# Power.net
KiCad netlist of a schematic drawn in Altium Designer
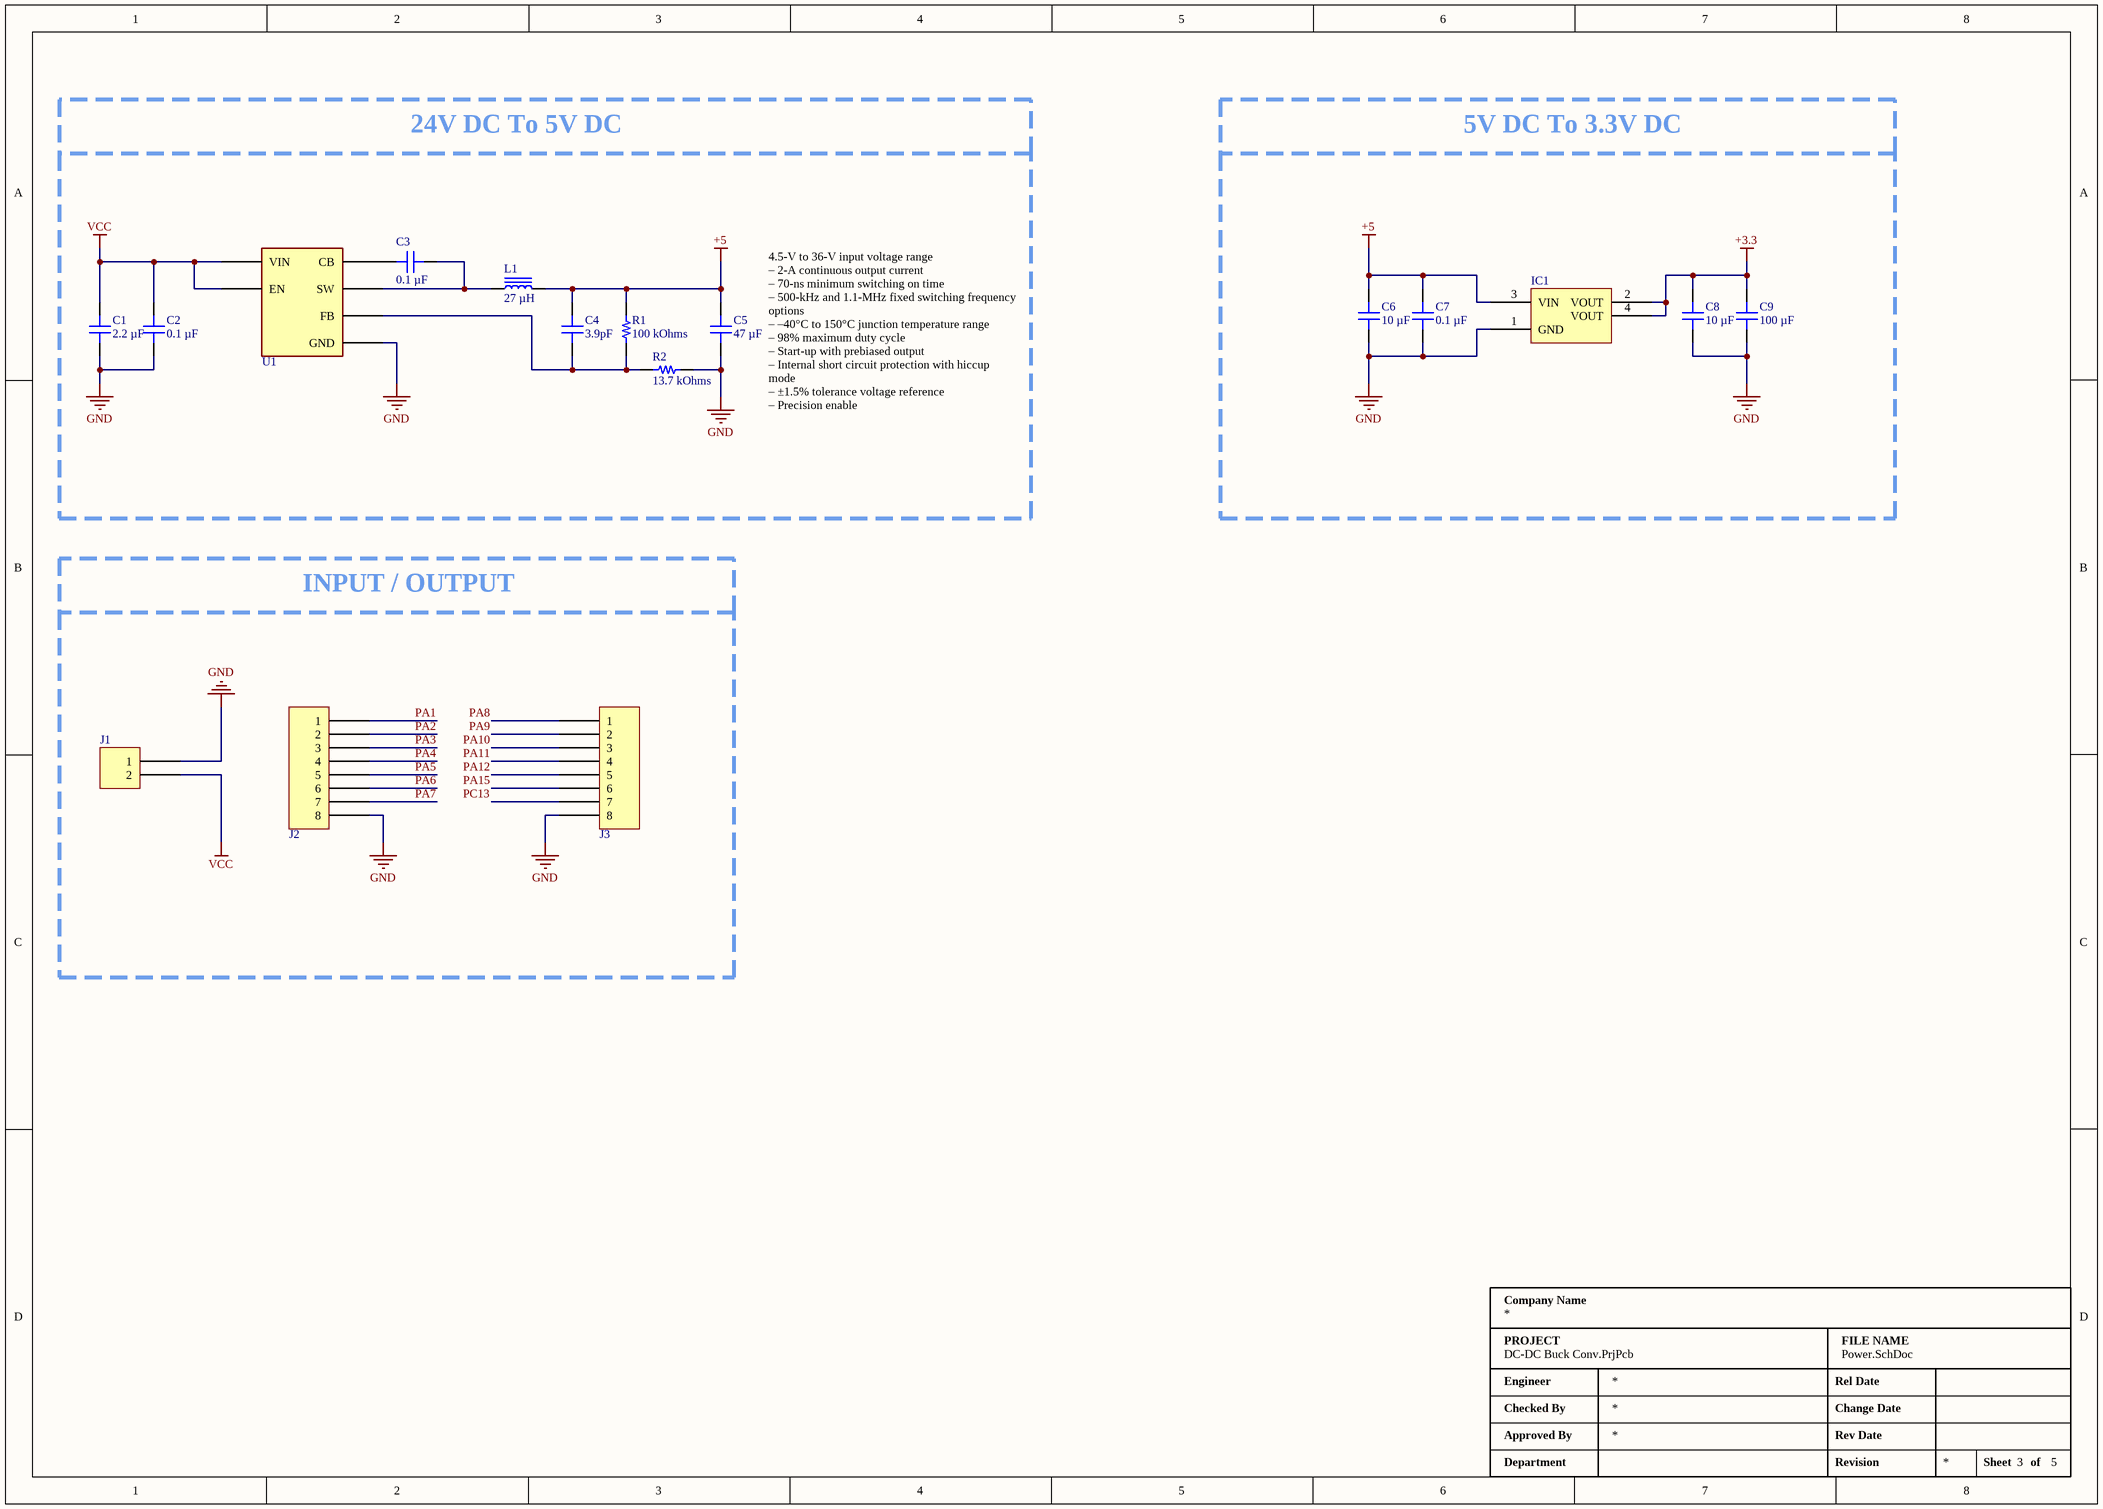
[diagram p0: Power.SchDoc]

(export (version "E")
  (design (tool "Eeschema 10.0.6"))
  (components
    (comp (ref "C1")
      (value "2.2 µF")
      (footprint "CAP 1206_3216 - 0.8MM")
      (description "CAP CER 2.2UF 50V X7R 1206")
      (fields
        (field (name "PART NUMBER") "CL31B225KBHVPNE")
        (field (name "CAPACITANCE") "2.2 µF")
        (field (name "MANUFACTURER") "Samsung Electro-Mechanics")
      )
      (libsource (lib "Celestial Altium Library - altium_library") (part "Capacitor"))
    )
    (comp (ref "C2")
      (value "0.1 µF")
      (footprint "CAP 0603_1608")
      (description "CAP CER 0603 0.1UF 50V X7R 10%")
      (fields
        (field (name "PART NUMBER") "C0603X104K5RAC3316")
        (field (name "CAPACITANCE") "0.1 µF")
        (field (name "MANUFACTURER") "KEMET")
      )
      (libsource (lib "Celestial Altium Library - altium_library") (part "Capacitor"))
    )
    (comp (ref "C3")
      (value "0.1 µF")
      (footprint "CAP 0402_1005")
      (description "CAP CER 0402 0.1UF 16V X7R 10%")
      (fields
        (field (name "PART NUMBER") "C0402C104K4RECAUTO")
        (field (name "CAPACITANCE") "0.1 µF")
        (field (name "MANUFACTURER") "KEMET")
      )
      (libsource (lib "Celestial Altium Library - altium_library") (part "Capacitor"))
    )
    (comp (ref "C4")
      (value "3.9pF")
      (footprint "CAP 0402_1005")
      (description "CAP CER 3.9PF 25V NP0 0402")
      (fields
        (field (name "PART NUMBER") "04023U3R9BAT2A")
        (field (name "CAPACITANCE") "3.9pF")
        (field (name "MANUFACTURER") "AVX Corporation")
      )
      (libsource (lib "Celestial Altium Library - altium_library") (part "Capacitor"))
    )
    (comp (ref "C5")
      (value "47 µF")
      (footprint "MURATA - GRM32E")
      (description "CAP CER 47UF 16V X6S 1210")
      (fields
        (field (name "PART NUMBER") "GRM32EC81C476KE15L")
        (field (name "MANUFACTURER") "Murata Electronics")
      )
      (libsource (lib "Celestial Altium Library - altium_library") (part "Capacitor"))
    )
    (comp (ref "C6")
      (value "10 µF")
      (footprint "MURATA GRM21B 0805_2012")
      (description "CAP CER 10UF 50V X5R 0805")
      (fields
        (field (name "PART NUMBER") "GRM21BR61H106KE43L")
        (field (name "CAPACITANCE") "10 µF")
        (field (name "MANUFACTURER") "Murata Electronics")
      )
      (libsource (lib "Celestial Altium Library - altium_library") (part "Capacitor"))
    )
    (comp (ref "C7")
      (value "0.1 µF")
      (footprint "CAP 0805_2012")
      (description "CAP CER 0805 0.1UF 100V X7R 5%")
      (fields
        (field (name "PART NUMBER") "C0805C104J1RECAUTO")
        (field (name "CAPACITANCE") "0.1 µF")
        (field (name "MANUFACTURER") "KEMET")
      )
      (libsource (lib "Celestial Altium Library - altium_library") (part "Capacitor"))
    )
    (comp (ref "C8")
      (value "10 µF")
      (footprint "MURATA GRM21B 0805_2012")
      (description "CAP CER 10UF 50V X5R 0805")
      (fields
        (field (name "PART NUMBER") "GRM21BR61H106KE43L")
        (field (name "CAPACITANCE") "10 µF")
        (field (name "MANUFACTURER") "Murata Electronics")
      )
      (libsource (lib "Celestial Altium Library - altium_library") (part "Capacitor"))
    )
    (comp (ref "C9")
      (value "100 µF")
      (footprint "MURATA GRM21B 0805_2012")
      (description "CAP CER 100UF 6.3V X5R 0805")
      (fields
        (field (name "PART NUMBER") "GRM21BR60J107ME15K")
        (field (name "CAPACITANCE") "100 µF")
        (field (name "MANUFACTURER") "Murata Electronics")
      )
      (libsource (lib "Celestial Altium Library - altium_library") (part "Capacitor"))
    )
    (comp (ref "IC1")
      (value "LD1117AS33TR")
      (footprint "ST SOT-223")
      (description "IC REG LINEAR 3.3V 1A SOT223")
      (fields (field (name "MANUFACTURER") "STMicroelectronics"))
      (libsource (lib "Celestial Altium Library - altium_library") (part "ST LD1117"))
    )
    (comp (ref "J1")
      (value "282837-2")
      (footprint "TE 282837-2")
      (description "TERM BLK 2P SIDE ENT 5.08MM PCB")
      (fields (field (name "MANUFACTURER") "TE Connectivity AMP Connectors") (field (name "VOLTAGE") "300 V"))
      (libsource (lib "Celestial Altium Library - altium_library") (part "2 Pin"))
    )
    (comp (ref "J2")
      (value "SSW-108-03-T-S")
      (footprint "SAMTEC SSW-108-03-T-S")
      (description "CONN RCPT 8POS 0.1 TIN PCB")
      (fields (field (name "MANUFACTURER") "Samtec Inc."))
      (libsource (lib "Celestial Altium Library - altium_library") (part "8 Pin"))
    )
    (comp (ref "J3")
      (value "SSW-108-03-T-S")
      (footprint "SAMTEC SSW-108-03-T-S")
      (description "CONN RCPT 8POS 0.1 TIN PCB")
      (fields (field (name "MANUFACTURER") "Samtec Inc."))
      (libsource (lib "") (part "8 Pin_1"))
    )
    (comp (ref "L1")
      (value "27 µH")
      (footprint "BOURNS SRR6028")
      (description "FIXED IND 27UH 1.2A 130 MOHM SMD")
      (fields (field (name "PART NUMBER") "SRR6028-270Y") (field (name "MANUFACTURER") "Bourns Inc."))
      (libsource (lib "Celestial Altium Library - altium_library") (part "Inductor"))
    )
    (comp (ref "R1")
      (value "100 kOhms")
      (footprint "YAGEO RES 0402_1005")
      (description "RES 162K OHM 1% 1/16W 0402")
      (fields (field (name "PART NUMBER") "RC0402FR-07162KL") (field (name "MANUFACTURER") "Yageo"))
      (libsource (lib "Celestial Altium Library - altium_library") (part "Resistor"))
    )
    (comp (ref "R2")
      (value "13.7 kOhms")
      (footprint "YAGEO RES 0402_1005")
      (description "RES 22.1K OHM 1% 1/16W 0402")
      (fields (field (name "PART NUMBER") "RC0402FR-0722K1L") (field (name "MANUFACTURER") "Yageo"))
      (libsource (lib "Celestial Altium Library - altium_library") (part "Resistor"))
    )
    (comp (ref "U1")
      (value "IC REG BUCK ADJ 2A SOT23")
      (footprint "SOT-23-6 Thin")
      (libsource (lib "DcDcBuck") (part "LMR51420XDDCR"))
    )
  )
  (nets
    (net (code "1") (name "+3.3") (class "Default")
      (node (ref "C8") (pin "2") (pinfunction "2_2") (pintype "passive"))
      (node (ref "C9") (pin "2") (pinfunction "2_2") (pintype "passive"))
      (node (ref "IC1") (pin "2") (pinfunction "VOUT_2") (pintype "passive"))
      (node (ref "IC1") (pin "4") (pinfunction "VOUT_4") (pintype "passive"))
    )
    (net (code "2") (name "+5") (class "Default")
      (node (ref "C4") (pin "1") (pinfunction "1_1") (pintype "passive"))
      (node (ref "C5") (pin "2") (pinfunction "2_2") (pintype "passive"))
      (node (ref "C6") (pin "2") (pinfunction "2_2") (pintype "passive"))
      (node (ref "C7") (pin "2") (pinfunction "2_2") (pintype "passive"))
      (node (ref "IC1") (pin "3") (pinfunction "VIN_3") (pintype "passive"))
      (node (ref "L1") (pin "2") (pinfunction "2_2") (pintype "passive"))
      (node (ref "R1") (pin "2") (pinfunction "2_2") (pintype "passive"))
    )
    (net (code "3") (name "/PA1") (class "Default")
      (node (ref "J2") (pin "1") (pinfunction "1_1") (pintype "passive"))
    )
    (net (code "4") (name "/PA2") (class "Default")
      (node (ref "J2") (pin "2") (pinfunction "2_2") (pintype "passive"))
    )
    (net (code "5") (name "/PA3") (class "Default")
      (node (ref "J2") (pin "3") (pinfunction "3_3") (pintype "passive"))
    )
    (net (code "6") (name "/PA4") (class "Default")
      (node (ref "J2") (pin "4") (pinfunction "4_4") (pintype "passive"))
    )
    (net (code "7") (name "/PA5") (class "Default")
      (node (ref "J2") (pin "5") (pinfunction "5_5") (pintype "passive"))
    )
    (net (code "8") (name "/PA6") (class "Default")
      (node (ref "J2") (pin "6") (pinfunction "6_6") (pintype "passive"))
    )
    (net (code "9") (name "/PA7") (class "Default")
      (node (ref "J2") (pin "7") (pinfunction "7_7") (pintype "passive"))
    )
    (net (code "10") (name "/PA8") (class "Default")
      (node (ref "J3") (pin "1") (pinfunction "1_1") (pintype "passive"))
    )
    (net (code "11") (name "/PA9") (class "Default")
      (node (ref "J3") (pin "2") (pinfunction "2_2") (pintype "passive"))
    )
    (net (code "12") (name "/PA10") (class "Default")
      (node (ref "J3") (pin "3") (pinfunction "3_3") (pintype "passive"))
    )
    (net (code "13") (name "/PA11") (class "Default")
      (node (ref "J3") (pin "4") (pinfunction "4_4") (pintype "passive"))
    )
    (net (code "14") (name "/PA12") (class "Default")
      (node (ref "J3") (pin "5") (pinfunction "5_5") (pintype "passive"))
    )
    (net (code "15") (name "/PA15") (class "Default")
      (node (ref "J3") (pin "6") (pinfunction "6_6") (pintype "passive"))
    )
    (net (code "16") (name "/PC13") (class "Default")
      (node (ref "J3") (pin "7") (pinfunction "7_7") (pintype "passive"))
    )
    (net (code "17") (name "GND") (class "Default")
      (node (ref "C1") (pin "1") (pinfunction "1_1") (pintype "passive"))
      (node (ref "C2") (pin "1") (pinfunction "1_1") (pintype "passive"))
      (node (ref "C5") (pin "1") (pinfunction "1_1") (pintype "passive"))
      (node (ref "C6") (pin "1") (pinfunction "1_1") (pintype "passive"))
      (node (ref "C7") (pin "1") (pinfunction "1_1") (pintype "passive"))
      (node (ref "C8") (pin "1") (pinfunction "1_1") (pintype "passive"))
      (node (ref "C9") (pin "1") (pinfunction "1_1") (pintype "passive"))
      (node (ref "IC1") (pin "1") (pinfunction "GND_1") (pintype "passive"))
      (node (ref "J1") (pin "1") (pinfunction "1_1") (pintype "passive"))
      (node (ref "J2") (pin "8") (pinfunction "8_8") (pintype "passive"))
      (node (ref "J3") (pin "8") (pinfunction "8_8") (pintype "passive"))
      (node (ref "R2") (pin "2") (pinfunction "2_2") (pintype "passive"))
      (node (ref "U1") (pin "1") (pinfunction "GND_1") (pintype "power_in"))
    )
    (net (code "18") (name "Net-(U1-CB)") (class "Default")
      (node (ref "C3") (pin "2") (pinfunction "2_2") (pintype "passive"))
      (node (ref "U1") (pin "6") (pinfunction "CB_6") (pintype "passive"))
    )
    (net (code "19") (name "Net-(U1-FB)") (class "Default")
      (node (ref "C4") (pin "2") (pinfunction "2_2") (pintype "passive"))
      (node (ref "R1") (pin "1") (pinfunction "1_1") (pintype "passive"))
      (node (ref "R2") (pin "1") (pinfunction "1_1") (pintype "passive"))
      (node (ref "U1") (pin "4") (pinfunction "FB_4") (pintype "passive"))
    )
    (net (code "20") (name "Net-(U1-SW)") (class "Default")
      (node (ref "C3") (pin "1") (pinfunction "1_1") (pintype "passive"))
      (node (ref "L1") (pin "1") (pinfunction "1_1") (pintype "passive"))
      (node (ref "U1") (pin "2") (pinfunction "SW_2") (pintype "passive"))
    )
    (net (code "21") (name "VCC") (class "Default")
      (node (ref "C1") (pin "2") (pinfunction "2_2") (pintype "passive"))
      (node (ref "C2") (pin "2") (pinfunction "2_2") (pintype "passive"))
      (node (ref "J1") (pin "2") (pinfunction "2_2") (pintype "passive"))
      (node (ref "U1") (pin "3") (pinfunction "VIN_3") (pintype "passive"))
      (node (ref "U1") (pin "5") (pinfunction "EN_5") (pintype "passive"))
    )
  )
)
